# Connections.net
KiCad netlist of a schematic drawn in Altium Designer
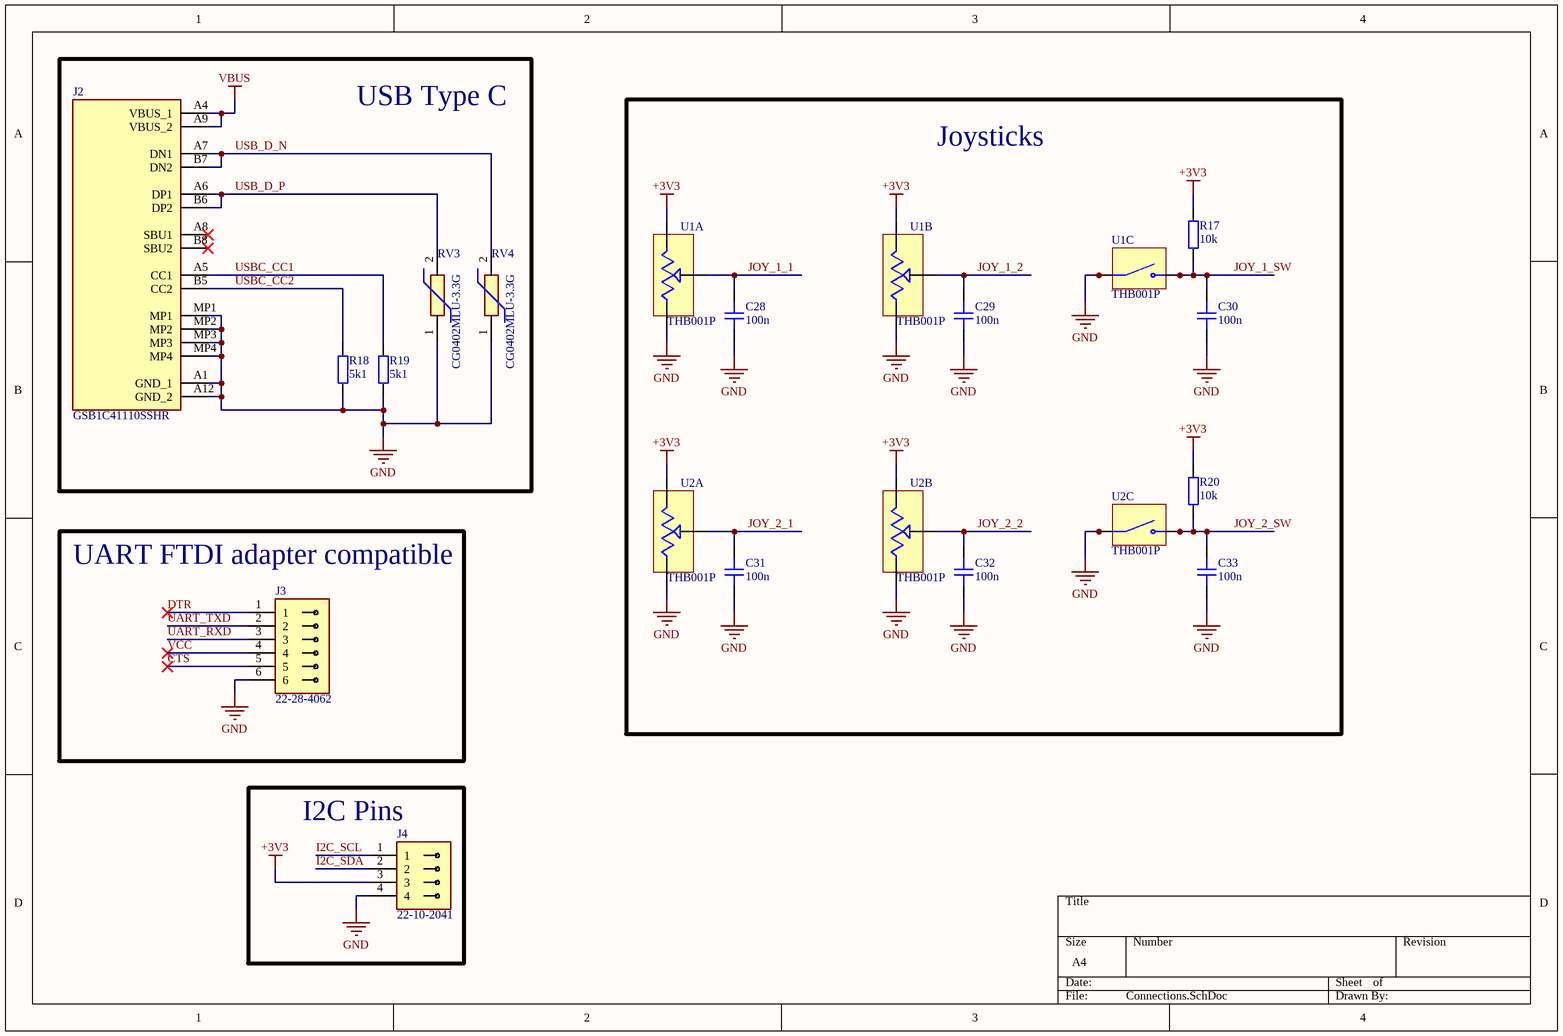
[diagram p0: Connections.SchDoc]

(export (version "E")
  (design (tool "Eeschema 10.0.6"))
  (components
    (comp (ref "C28")
      (value "100n")
      (footprint "CAP_0402")
      (description "Capacitor SMD 0402")
      (libsource (lib "Schematic-Lib-PhilsLab") (part "CAP_0402"))
    )
    (comp (ref "C29")
      (value "100n")
      (footprint "CAP_0402")
      (description "Capacitor SMD 0402")
      (libsource (lib "Schematic-Lib-PhilsLab") (part "CAP_0402"))
    )
    (comp (ref "C30")
      (value "100n")
      (footprint "CAP_0402")
      (description "Capacitor SMD 0402")
      (libsource (lib "Schematic-Lib-PhilsLab") (part "CAP_0402"))
    )
    (comp (ref "C31")
      (value "100n")
      (footprint "CAP_0402")
      (description "Capacitor SMD 0402")
      (libsource (lib "Schematic-Lib-PhilsLab") (part "CAP_0402"))
    )
    (comp (ref "C32")
      (value "100n")
      (footprint "CAP_0402")
      (description "Capacitor SMD 0402")
      (libsource (lib "Schematic-Lib-PhilsLab") (part "CAP_0402"))
    )
    (comp (ref "C33")
      (value "100n")
      (footprint "CAP_0402")
      (description "Capacitor SMD 0402")
      (libsource (lib "Schematic-Lib-PhilsLab") (part "CAP_0402"))
    )
    (comp (ref "J2")
      (value "GSB1C41110SSHR")
      (footprint "Footprint-Lib-PhilsLab:GSB1C41110SSHR")
      (description "Connector")
      (libsource (lib "Schematic-Lib-PhilsLab") (part "GSB1C41110SSHR"))
    )
    (comp (ref "J3")
      (value "22-28-4062")
      (footprint "Footprint-Lib-PhilsLab:HDRV6W66P0X254_1X6_1524X249X838P")
      (description "Connector")
      (fields (field (name "MOUSER PART NUMBER") "538-22-28-4062"))
      (libsource (lib "Schematic-Lib-PhilsLab") (part "22-28-4062"))
    )
    (comp (ref "J4")
      (value "22-10-2041")
      (footprint "Footprint-Lib-PhilsLab:HDRV4W67P0X254_1X4_991X236X1117P")
      (description "Connector")
      (fields (field (name "MOUSER PART NUMBER") "538-22-10-2041"))
      (libsource (lib "Schematic-Lib-PhilsLab") (part "22-10-2041"))
    )
    (comp (ref "R17")
      (value "10k")
      (footprint "RES_0402")
      (description "Resistor SMD 0402")
      (libsource (lib "Schematic-Lib-PhilsLab") (part "RES_0402"))
    )
    (comp (ref "R18")
      (value "5k1")
      (footprint "RES_0402")
      (description "Resistor SMD 0402")
      (libsource (lib "Schematic-Lib-PhilsLab") (part "RES_0402"))
    )
    (comp (ref "R19")
      (value "5k1")
      (footprint "RES_0402")
      (description "Resistor SMD 0402")
      (libsource (lib "Schematic-Lib-PhilsLab") (part "RES_0402"))
    )
    (comp (ref "R20")
      (value "10k")
      (footprint "RES_0402")
      (description "Resistor SMD 0402")
      (libsource (lib "Schematic-Lib-PhilsLab") (part "RES_0402"))
    )
    (comp (ref "RV3")
      (value "CG0402MLU-3.3G")
      (footprint "Footprint-Lib-PhilsLab:VARC1005X41N")
      (description "ESD Diode")
      (fields (field (name "MOUSER PART NUMBER") "652-CG0402MLU-3.3G"))
      (libsource (lib "Schematic-Lib-PhilsLab") (part "CG0402MLU-3.3G"))
    )
    (comp (ref "RV4")
      (value "CG0402MLU-3.3G")
      (footprint "Footprint-Lib-PhilsLab:VARC1005X41N")
      (description "ESD Diode")
      (fields (field (name "MOUSER PART NUMBER") "652-CG0402MLU-3.3G"))
      (libsource (lib "Schematic-Lib-PhilsLab") (part "CG0402MLU-3.3G"))
    )
    (comp (ref "U1")
      (value "THB001P")
      (footprint "CNK_THB001P")
      (description "Joystick, 2 - Axis Analog (Resistive) Output")
      (fields (field (name "MF") "C&K"))
      (libsource (lib "Schematic-Lib-PhilsLab") (part "THB001P"))
    )
    (comp (ref "U2")
      (value "THB001P")
      (footprint "CNK_THB001P")
      (description "Joystick, 2 - Axis Analog (Resistive) Output")
      (fields (field (name "MF") "C&K"))
      (libsource (lib "Schematic-Lib-PhilsLab") (part "THB001P"))
    )
  )
  (nets
    (net (code "1") (name "+3V3") (class "Default")
      (node (ref "J4") (pin "3") (pinfunction "3_3") (pintype "passive"))
      (node (ref "R17") (pin "1") (pinfunction "1_1") (pintype "passive"))
      (node (ref "R20") (pin "1") (pinfunction "1_1") (pintype "passive"))
      (node (ref "U1") (pin "VR1_1") (pinfunction "VR1_1_VR1_1") (pintype "passive"))
      (node (ref "U1") (pin "VR2_1") (pinfunction "VR2_1_VR2_1") (pintype "passive"))
      (node (ref "U2") (pin "VR1_1") (pinfunction "VR1_1_VR1_1") (pintype "passive"))
      (node (ref "U2") (pin "VR2_1") (pinfunction "VR2_1_VR2_1") (pintype "passive"))
    )
    (net (code "2") (name "/CTS") (class "Default")
      (node (ref "J3") (pin "5") (pinfunction "5_5") (pintype "passive+no_connect"))
    )
    (net (code "3") (name "/DTR") (class "Default")
      (node (ref "J3") (pin "1") (pinfunction "1_1") (pintype "passive+no_connect"))
    )
    (net (code "4") (name "/I2C_SCL") (class "Default")
      (node (ref "J4") (pin "1") (pinfunction "1_1") (pintype "passive"))
    )
    (net (code "5") (name "/I2C_SDA") (class "Default")
      (node (ref "J4") (pin "2") (pinfunction "2_2") (pintype "passive"))
    )
    (net (code "6") (name "/JOY_1_1") (class "Default")
      (node (ref "C28") (pin "1") (pinfunction "1_1") (pintype "passive"))
      (node (ref "U1") (pin "VR1_2") (pinfunction "VR1_2_VR1_2") (pintype "passive"))
    )
    (net (code "7") (name "/JOY_1_2") (class "Default")
      (node (ref "C29") (pin "1") (pinfunction "1_1") (pintype "passive"))
      (node (ref "U1") (pin "VR2_2") (pinfunction "VR2_2_VR2_2") (pintype "passive"))
    )
    (net (code "8") (name "/JOY_1_SW") (class "Default")
      (node (ref "C30") (pin "1") (pinfunction "1_1") (pintype "passive"))
      (node (ref "R17") (pin "2") (pinfunction "2_2") (pintype "passive"))
      (node (ref "U1") (pin "A") (pinfunction "NO_A") (pintype "passive"))
      (node (ref "U1") (pin "B") (pinfunction "NO_B") (pintype "passive"))
    )
    (net (code "9") (name "/JOY_2_1") (class "Default")
      (node (ref "C31") (pin "1") (pinfunction "1_1") (pintype "passive"))
      (node (ref "U2") (pin "VR1_2") (pinfunction "VR1_2_VR1_2") (pintype "passive"))
    )
    (net (code "10") (name "/JOY_2_2") (class "Default")
      (node (ref "C32") (pin "1") (pinfunction "1_1") (pintype "passive"))
      (node (ref "U2") (pin "VR2_2") (pinfunction "VR2_2_VR2_2") (pintype "passive"))
    )
    (net (code "11") (name "/JOY_2_SW") (class "Default")
      (node (ref "C33") (pin "1") (pinfunction "1_1") (pintype "passive"))
      (node (ref "R20") (pin "2") (pinfunction "2_2") (pintype "passive"))
      (node (ref "U2") (pin "A") (pinfunction "NO_A") (pintype "passive"))
      (node (ref "U2") (pin "B") (pinfunction "NO_B") (pintype "passive"))
    )
    (net (code "12") (name "/UART_RXD") (class "Default")
      (node (ref "J3") (pin "3") (pinfunction "3_3") (pintype "passive"))
    )
    (net (code "13") (name "/UART_TXD") (class "Default")
      (node (ref "J3") (pin "2") (pinfunction "2_2") (pintype "passive"))
    )
    (net (code "14") (name "/USBC_CC1") (class "Default")
      (node (ref "J2") (pin "A5") (pinfunction "CC1_A5") (pintype "passive"))
      (node (ref "R19") (pin "2") (pinfunction "2_2") (pintype "passive"))
    )
    (net (code "15") (name "/USBC_CC2") (class "Default")
      (node (ref "J2") (pin "B5") (pinfunction "CC2_B5") (pintype "passive"))
      (node (ref "R18") (pin "2") (pinfunction "2_2") (pintype "passive"))
    )
    (net (code "16") (name "/USB_D_N") (class "Default")
      (node (ref "J2") (pin "A7") (pinfunction "DN1_A7") (pintype "passive"))
      (node (ref "J2") (pin "B7") (pinfunction "DN2_B7") (pintype "passive"))
      (node (ref "RV4") (pin "2") (pinfunction "2_2") (pintype "passive"))
    )
    (net (code "17") (name "/USB_D_P") (class "Default")
      (node (ref "J2") (pin "A6") (pinfunction "DP1_A6") (pintype "passive"))
      (node (ref "J2") (pin "B6") (pinfunction "DP2_B6") (pintype "passive"))
      (node (ref "RV3") (pin "2") (pinfunction "2_2") (pintype "passive"))
    )
    (net (code "18") (name "/VCC") (class "Default")
      (node (ref "J3") (pin "4") (pinfunction "4_4") (pintype "passive+no_connect"))
    )
    (net (code "19") (name "GND") (class "Default")
      (node (ref "C28") (pin "2") (pinfunction "2_2") (pintype "passive"))
      (node (ref "C29") (pin "2") (pinfunction "2_2") (pintype "passive"))
      (node (ref "C30") (pin "2") (pinfunction "2_2") (pintype "passive"))
      (node (ref "C31") (pin "2") (pinfunction "2_2") (pintype "passive"))
      (node (ref "C32") (pin "2") (pinfunction "2_2") (pintype "passive"))
      (node (ref "C33") (pin "2") (pinfunction "2_2") (pintype "passive"))
      (node (ref "J2") (pin "A1") (pinfunction "GND_1_A1") (pintype "passive"))
      (node (ref "J2") (pin "A12") (pinfunction "GND_2_A12") (pintype "passive"))
      (node (ref "J2") (pin "MP1") (pinfunction "MP1_MP1") (pintype "passive"))
      (node (ref "J2") (pin "MP2") (pinfunction "MP2_MP2") (pintype "passive"))
      (node (ref "J2") (pin "MP3") (pinfunction "MP3_MP3") (pintype "passive"))
      (node (ref "J2") (pin "MP4") (pinfunction "MP4_MP4") (pintype "passive"))
      (node (ref "J3") (pin "6") (pinfunction "6_6") (pintype "passive"))
      (node (ref "J4") (pin "4") (pinfunction "4_4") (pintype "passive"))
      (node (ref "R18") (pin "1") (pinfunction "1_1") (pintype "passive"))
      (node (ref "R19") (pin "1") (pinfunction "1_1") (pintype "passive"))
      (node (ref "RV3") (pin "1") (pinfunction "1_1") (pintype "passive"))
      (node (ref "RV4") (pin "1") (pinfunction "1_1") (pintype "passive"))
      (node (ref "U1") (pin "C") (pinfunction "COM_C") (pintype "passive"))
      (node (ref "U1") (pin "D") (pinfunction "COM_D") (pintype "passive"))
      (node (ref "U1") (pin "VR1_3") (pinfunction "VR1_3_VR1_3") (pintype "passive"))
      (node (ref "U1") (pin "VR2_3") (pinfunction "VR2_3_VR2_3") (pintype "passive"))
      (node (ref "U2") (pin "C") (pinfunction "COM_C") (pintype "passive"))
      (node (ref "U2") (pin "D") (pinfunction "COM_D") (pintype "passive"))
      (node (ref "U2") (pin "VR1_3") (pinfunction "VR1_3_VR1_3") (pintype "passive"))
      (node (ref "U2") (pin "VR2_3") (pinfunction "VR2_3_VR2_3") (pintype "passive"))
    )
    (net (code "20") (name "VBUS") (class "Default")
      (node (ref "J2") (pin "A4") (pinfunction "VBUS_1_A4") (pintype "passive"))
      (node (ref "J2") (pin "A9") (pinfunction "VBUS_2_A9") (pintype "passive"))
    )
    (net (code "21") (name "unconnected-(J2-SBU1-PadA8)") (class "Default")
      (node (ref "J2") (pin "A8") (pinfunction "SBU1_A8") (pintype "passive+no_connect"))
    )
    (net (code "22") (name "unconnected-(J2-SBU2-PadB8)") (class "Default")
      (node (ref "J2") (pin "B8") (pinfunction "SBU2_B8") (pintype "passive+no_connect"))
    )
  )
)
